# W028X.net
KiCad netlist of a schematic drawn in EAGLE
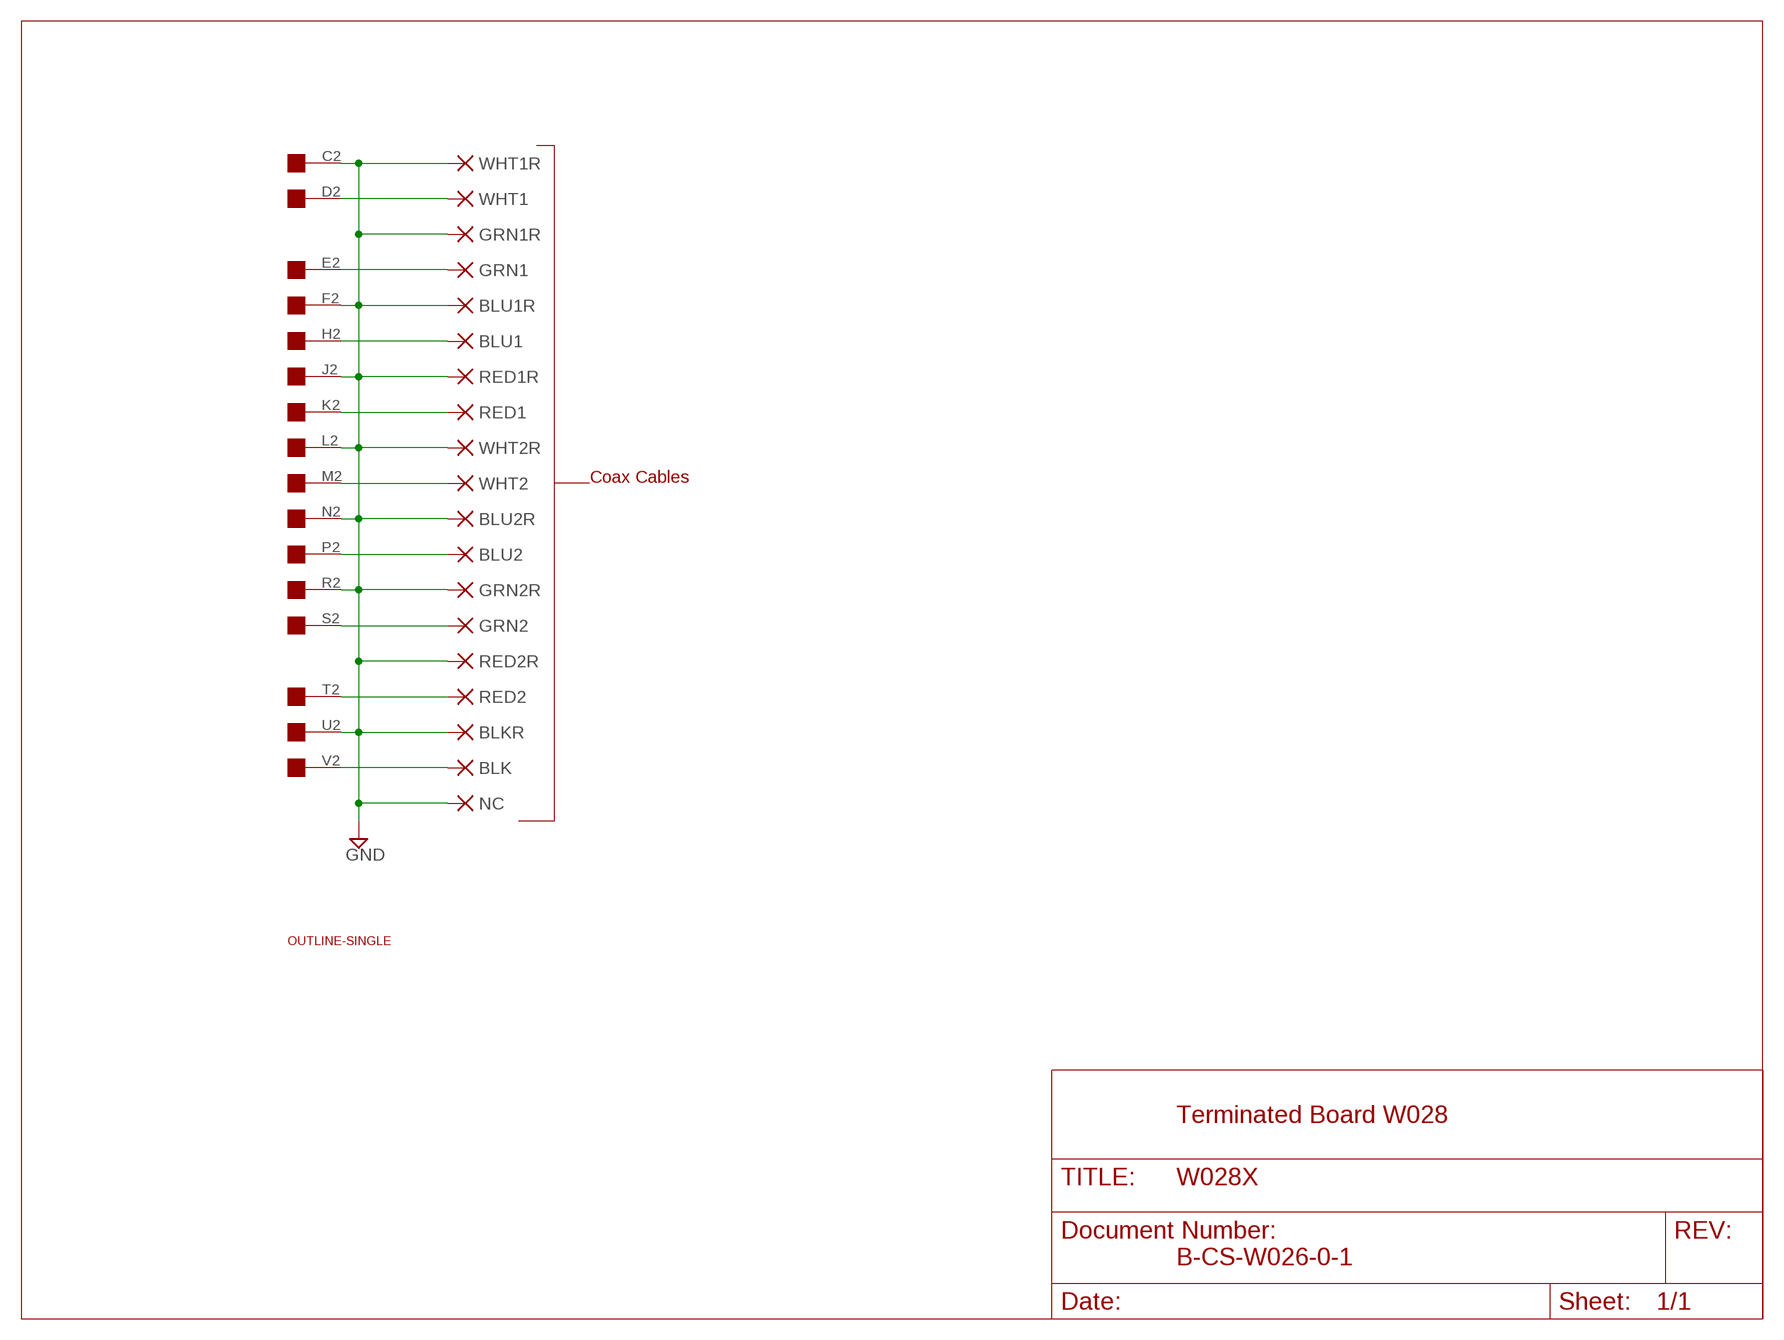
[diagram p0: schematic, sheet 1]

(export (version "E")
  (design (tool "Eeschema 10.0.6"))
  (components
    (comp (ref "BLK")
      (value "PAD-0465")
      (footprint "eagle-import:0465")
      (libsource (lib "eagle-import") (part "PAD-0465"))
    )
    (comp (ref "BLKR")
      (value "PAD-0465")
      (footprint "eagle-import:0465")
      (libsource (lib "eagle-import") (part "PAD-0465"))
    )
    (comp (ref "BLU1")
      (value "PAD-0465")
      (footprint "eagle-import:0465")
      (libsource (lib "eagle-import") (part "PAD-0465"))
    )
    (comp (ref "BLU1R")
      (value "PAD-0465")
      (footprint "eagle-import:0465")
      (libsource (lib "eagle-import") (part "PAD-0465"))
    )
    (comp (ref "BLU2")
      (value "PAD-0465")
      (footprint "eagle-import:0465")
      (libsource (lib "eagle-import") (part "PAD-0465"))
    )
    (comp (ref "BLU2R")
      (value "PAD-0465")
      (footprint "eagle-import:0465")
      (libsource (lib "eagle-import") (part "PAD-0465"))
    )
    (comp (ref "GRN1")
      (value "PAD-0465")
      (footprint "eagle-import:0465")
      (libsource (lib "eagle-import") (part "PAD-0465"))
    )
    (comp (ref "GRN1R")
      (value "PAD-0465")
      (footprint "eagle-import:0465")
      (libsource (lib "eagle-import") (part "PAD-0465"))
    )
    (comp (ref "GRN2")
      (value "PAD-0465")
      (footprint "eagle-import:0465")
      (libsource (lib "eagle-import") (part "PAD-0465"))
    )
    (comp (ref "GRN2R")
      (value "PAD-0465")
      (footprint "eagle-import:0465")
      (libsource (lib "eagle-import") (part "PAD-0465"))
    )
    (comp (ref "NC")
      (value "PAD-0465")
      (footprint "eagle-import:0465")
      (libsource (lib "eagle-import") (part "PAD-0465"))
    )
    (comp (ref "RED1")
      (value "PAD-0465")
      (footprint "eagle-import:0465")
      (libsource (lib "eagle-import") (part "PAD-0465"))
    )
    (comp (ref "RED1R")
      (value "PAD-0465")
      (footprint "eagle-import:0465")
      (libsource (lib "eagle-import") (part "PAD-0465"))
    )
    (comp (ref "RED2")
      (value "PAD-0465")
      (footprint "eagle-import:0465")
      (libsource (lib "eagle-import") (part "PAD-0465"))
    )
    (comp (ref "RED2R")
      (value "PAD-0465")
      (footprint "eagle-import:0465")
      (libsource (lib "eagle-import") (part "PAD-0465"))
    )
    (comp (ref "U$1")
      (value "OUTLINE-SINGLE")
      (footprint "eagle-import:SINGLE")
      (libsource (lib "eagle-import") (part "OUTLINE-SINGLE"))
    )
    (comp (ref "U$2")
      (value "EDGE-1")
      (footprint "eagle-import:EDGE-CON1")
      (libsource (lib "eagle-import") (part "EDGE-1"))
    )
    (comp (ref "WHT1")
      (value "PAD-0465")
      (footprint "eagle-import:0465")
      (libsource (lib "eagle-import") (part "PAD-0465"))
    )
    (comp (ref "WHT1R")
      (value "PAD-0465")
      (footprint "eagle-import:0465")
      (libsource (lib "eagle-import") (part "PAD-0465"))
    )
    (comp (ref "WHT2")
      (value "PAD-0465")
      (footprint "eagle-import:0465")
      (libsource (lib "eagle-import") (part "PAD-0465"))
    )
    (comp (ref "WHT2R")
      (value "PAD-0465")
      (footprint "eagle-import:0465")
      (libsource (lib "eagle-import") (part "PAD-0465"))
    )
  )
  (nets
    (net (code "1") (name "GND") (class "Default")
      (node (ref "BLKR") (pin "P$1") (pinfunction "P_P$1") (pintype "passive"))
      (node (ref "BLU1R") (pin "P$1") (pinfunction "P_P$1") (pintype "passive"))
      (node (ref "BLU2R") (pin "P$1") (pinfunction "P_P$1") (pintype "passive"))
      (node (ref "GRN1R") (pin "P$1") (pinfunction "P_P$1") (pintype "passive"))
      (node (ref "GRN2R") (pin "P$1") (pinfunction "P_P$1") (pintype "passive"))
      (node (ref "NC") (pin "P$1") (pinfunction "P_P$1") (pintype "passive"))
      (node (ref "RED1R") (pin "P$1") (pinfunction "P_P$1") (pintype "passive"))
      (node (ref "RED2R") (pin "P$1") (pinfunction "P_P$1") (pintype "passive"))
      (node (ref "U$2") (pin "C2") (pinfunction "1_C2") (pintype "bidirectional"))
      (node (ref "U$2") (pin "F2") (pinfunction "1_F2") (pintype "bidirectional"))
      (node (ref "U$2") (pin "J2") (pinfunction "1_J2") (pintype "bidirectional"))
      (node (ref "U$2") (pin "L2") (pinfunction "1_L2") (pintype "bidirectional"))
      (node (ref "U$2") (pin "N2") (pinfunction "1_N2") (pintype "bidirectional"))
      (node (ref "U$2") (pin "R2") (pinfunction "1_R2") (pintype "bidirectional"))
      (node (ref "U$2") (pin "U2") (pinfunction "1_U2") (pintype "bidirectional"))
      (node (ref "WHT1R") (pin "P$1") (pinfunction "P_P$1") (pintype "passive"))
      (node (ref "WHT2R") (pin "P$1") (pinfunction "P_P$1") (pintype "passive"))
    )
    (net (code "2") (name "Net-(BLK-P)") (class "Default")
      (node (ref "BLK") (pin "P$1") (pinfunction "P_P$1") (pintype "passive"))
      (node (ref "U$2") (pin "V2") (pinfunction "1_V2") (pintype "bidirectional"))
    )
    (net (code "3") (name "Net-(BLU1-P)") (class "Default")
      (node (ref "BLU1") (pin "P$1") (pinfunction "P_P$1") (pintype "passive"))
      (node (ref "U$2") (pin "H2") (pinfunction "1_H2") (pintype "bidirectional"))
    )
    (net (code "4") (name "Net-(BLU2-P)") (class "Default")
      (node (ref "BLU2") (pin "P$1") (pinfunction "P_P$1") (pintype "passive"))
      (node (ref "U$2") (pin "P2") (pinfunction "1_P2") (pintype "bidirectional"))
    )
    (net (code "5") (name "Net-(GRN1-P)") (class "Default")
      (node (ref "GRN1") (pin "P$1") (pinfunction "P_P$1") (pintype "passive"))
      (node (ref "U$2") (pin "E2") (pinfunction "1_E2") (pintype "bidirectional"))
    )
    (net (code "6") (name "Net-(GRN2-P)") (class "Default")
      (node (ref "GRN2") (pin "P$1") (pinfunction "P_P$1") (pintype "passive"))
      (node (ref "U$2") (pin "S2") (pinfunction "1_S2") (pintype "bidirectional"))
    )
    (net (code "7") (name "Net-(RED1-P)") (class "Default")
      (node (ref "RED1") (pin "P$1") (pinfunction "P_P$1") (pintype "passive"))
      (node (ref "U$2") (pin "K2") (pinfunction "1_K2") (pintype "bidirectional"))
    )
    (net (code "8") (name "Net-(RED2-P)") (class "Default")
      (node (ref "RED2") (pin "P$1") (pinfunction "P_P$1") (pintype "passive"))
      (node (ref "U$2") (pin "T2") (pinfunction "1_T2") (pintype "bidirectional"))
    )
    (net (code "9") (name "Net-(U$2D-1)") (class "Default")
      (node (ref "U$2") (pin "D2") (pinfunction "1_D2") (pintype "bidirectional"))
      (node (ref "WHT1") (pin "P$1") (pinfunction "P_P$1") (pintype "passive"))
    )
    (net (code "10") (name "Net-(U$2K-1)") (class "Default")
      (node (ref "U$2") (pin "M2") (pinfunction "1_M2") (pintype "bidirectional"))
      (node (ref "WHT2") (pin "P$1") (pinfunction "P_P$1") (pintype "passive"))
    )
  )
)
